# Low_Distortion_Oscillator_Amp3.net
KiCad netlist of a schematic drawn in Altium Designer
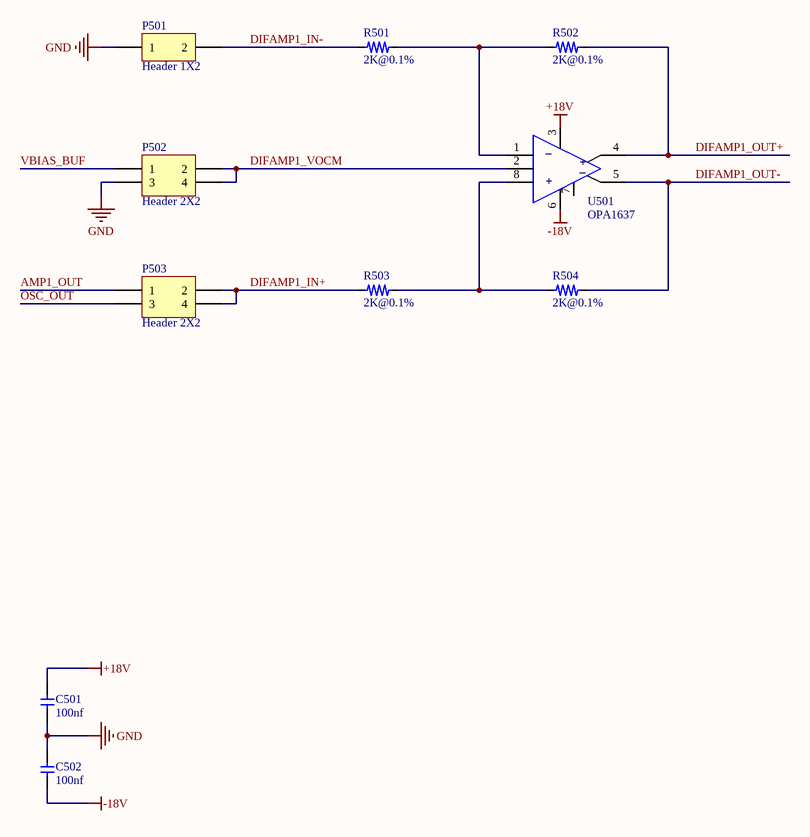
[diagram p0: Low Distortion Oscillator.Amp3.SchDoc]

(export (version "E")
  (design (tool "Eeschema 10.0.6"))
  (components
    (comp (ref "C501")
      (value "100nf")
      (footprint "C0805")
      (fields (field (name "Comment") "Cap"))
      (libsource (lib "carrot_lib") (part "Cap"))
    )
    (comp (ref "C502")
      (value "100nf")
      (footprint "C0805")
      (fields (field (name "Comment") "Cap"))
      (libsource (lib "carrot_lib") (part "Cap"))
    )
    (comp (ref "P501")
      (value "Header 1X2")
      (footprint "HDR2X1")
      (description "Header, 1-Pin, Dual row")
      (libsource (lib "carrot_lib") (part "Header 1X2"))
    )
    (comp (ref "P502")
      (value "Header 2X2")
      (footprint "HDR2X2")
      (description "Header, 2-Pin, Dual row")
      (libsource (lib "carrot_lib") (part "Header 2X2"))
    )
    (comp (ref "P503")
      (value "Header 2X2")
      (footprint "HDR2X2")
      (description "Header, 2-Pin, Dual row")
      (libsource (lib "carrot_lib") (part "Header 2X2"))
    )
    (comp (ref "R501")
      (value "2K@0.1%")
      (footprint "R0805")
      (description "电阻")
      (fields (field (name "Comment") "Res"))
      (libsource (lib "carrot_lib") (part "Res"))
    )
    (comp (ref "R502")
      (value "2K@0.1%")
      (footprint "R0805")
      (description "电阻")
      (fields (field (name "Comment") "Res"))
      (libsource (lib "carrot_lib") (part "Res"))
    )
    (comp (ref "R503")
      (value "2K@0.1%")
      (footprint "R0805")
      (description "电阻")
      (fields (field (name "Comment") "Res"))
      (libsource (lib "carrot_lib") (part "Res"))
    )
    (comp (ref "R504")
      (value "2K@0.1%")
      (footprint "R0805")
      (description "电阻")
      (fields (field (name "Comment") "Res"))
      (libsource (lib "carrot_lib") (part "Res"))
    )
    (comp (ref "U501")
      (value "OPA1637")
      (footprint "OPA1637-VSSOP8")
      (description "OPA1637 High-Fidelity, Low-Noise, Fully-Differential, Burr-Brown™ Audio Operational Amplifier")
      (libsource (lib "carrot_lib") (part "OPA1637"))
    )
  )
  (nets
    (net (code "1") (name "+18V") (class "Default")
      (node (ref "C501") (pin "2") (pinfunction "2_2") (pintype "passive"))
      (node (ref "U501") (pin "3") (pinfunction "+Vs_3") (pintype "passive"))
    )
    (net (code "2") (name "-18V") (class "Default")
      (node (ref "C502") (pin "1") (pinfunction "1_1") (pintype "passive"))
      (node (ref "U501") (pin "6") (pinfunction "-Vs_6") (pintype "passive"))
    )
    (net (code "3") (name "/AMP1_OUT") (class "Default")
      (node (ref "P503") (pin "1") (pinfunction "1_1") (pintype "passive"))
    )
    (net (code "4") (name "/DIFAMP1_IN+") (class "Default")
      (node (ref "P503") (pin "2") (pinfunction "2_2") (pintype "passive"))
      (node (ref "P503") (pin "4") (pinfunction "4_4") (pintype "passive"))
      (node (ref "R503") (pin "2") (pinfunction "2_2") (pintype "passive"))
    )
    (net (code "5") (name "/DIFAMP1_IN-") (class "Default")
      (node (ref "P501") (pin "2") (pinfunction "2_2") (pintype "passive"))
      (node (ref "R501") (pin "2") (pinfunction "2_2") (pintype "passive"))
    )
    (net (code "6") (name "/DIFAMP1_OUT+") (class "Default")
      (node (ref "R502") (pin "1") (pinfunction "1_1") (pintype "passive"))
      (node (ref "U501") (pin "4") (pinfunction "OUT+_4") (pintype "passive"))
    )
    (net (code "7") (name "/DIFAMP1_OUT-") (class "Default")
      (node (ref "R504") (pin "1") (pinfunction "1_1") (pintype "passive"))
      (node (ref "U501") (pin "5") (pinfunction "OUT-_5") (pintype "passive"))
    )
    (net (code "8") (name "/DIFAMP1_VOCM") (class "Default")
      (node (ref "P502") (pin "2") (pinfunction "2_2") (pintype "passive"))
      (node (ref "P502") (pin "4") (pinfunction "4_4") (pintype "passive"))
      (node (ref "U501") (pin "2") (pinfunction "VOCM_2") (pintype "passive"))
    )
    (net (code "9") (name "/OSC_OUT") (class "Default")
      (node (ref "P503") (pin "3") (pinfunction "3_3") (pintype "passive"))
    )
    (net (code "10") (name "/VBIAS_BUF") (class "Default")
      (node (ref "P502") (pin "1") (pinfunction "1_1") (pintype "passive"))
    )
    (net (code "11") (name "GND") (class "Default")
      (node (ref "C501") (pin "1") (pinfunction "1_1") (pintype "passive"))
      (node (ref "C502") (pin "2") (pinfunction "2_2") (pintype "passive"))
      (node (ref "P501") (pin "1") (pinfunction "1_1") (pintype "passive"))
      (node (ref "P502") (pin "3") (pinfunction "3_3") (pintype "passive"))
    )
    (net (code "12") (name "Net-(U501-+IN)") (class "Default")
      (node (ref "R503") (pin "1") (pinfunction "1_1") (pintype "passive"))
      (node (ref "R504") (pin "2") (pinfunction "2_2") (pintype "passive"))
      (node (ref "U501") (pin "8") (pinfunction "+IN_8") (pintype "passive"))
    )
    (net (code "13") (name "Net-(U501--IN)") (class "Default")
      (node (ref "R501") (pin "1") (pinfunction "1_1") (pintype "passive"))
      (node (ref "R502") (pin "2") (pinfunction "2_2") (pintype "passive"))
      (node (ref "U501") (pin "1") (pinfunction "-IN_1") (pintype "passive"))
    )
    (net (code "14") (name "unconnected-(U501-~{PD}-Pad7)") (class "Default")
      (node (ref "U501") (pin "7") (pinfunction "~{PD}_7") (pintype "passive"))
    )
  )
)
